# floor.net
KiCad netlist of a schematic drawn in EAGLE
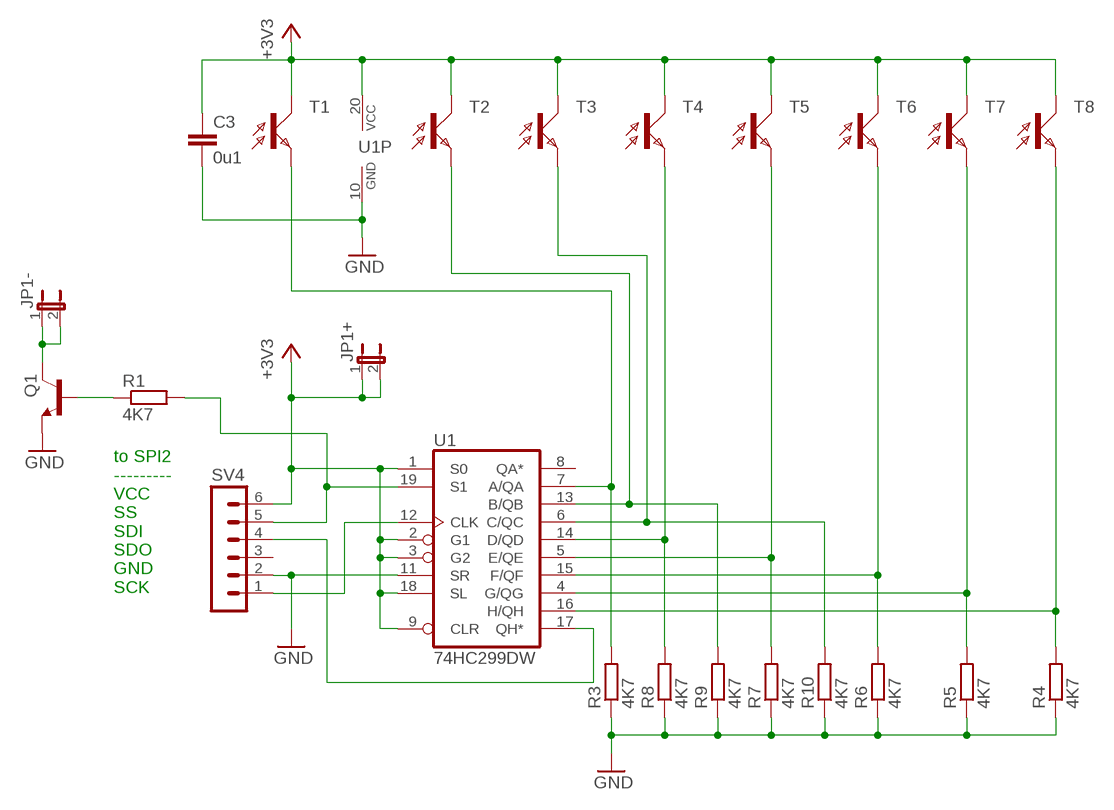
[diagram p0: schematic, sheet 1]

(export (version "E")
  (design (tool "Eeschema 10.0.6"))
  (components
    (comp (ref "C3")
      (value "0u1")
      (footprint "eagle-import:C0805")
      (libsource (lib "eagle-import") (part "C-EUC0805"))
    )
    (comp (ref "JP1+")
      (value "JP1E")
      (footprint "eagle-import:JP1")
      (libsource (lib "eagle-import") (part "JP1E"))
    )
    (comp (ref "JP1-")
      (value "JP1E")
      (footprint "eagle-import:JP1")
      (libsource (lib "eagle-import") (part "JP1E"))
    )
    (comp (ref "Q1")
      (value "BC817-25SMD")
      (footprint "eagle-import:SOT23-BEC")
      (libsource (lib "eagle-import") (part "BC817SMD-25"))
    )
    (comp (ref "R1")
      (value "4K7")
      (footprint "eagle-import:M0805")
      (libsource (lib "eagle-import") (part "R-EU_M0805"))
    )
    (comp (ref "R3")
      (value "4K7")
      (footprint "eagle-import:M0805")
      (libsource (lib "eagle-import") (part "R-EU_M0805"))
    )
    (comp (ref "R4")
      (value "4K7")
      (footprint "eagle-import:M0805")
      (libsource (lib "eagle-import") (part "R-EU_M0805"))
    )
    (comp (ref "R5")
      (value "4K7")
      (footprint "eagle-import:M0805")
      (libsource (lib "eagle-import") (part "R-EU_M0805"))
    )
    (comp (ref "R6")
      (value "4K7")
      (footprint "eagle-import:M0805")
      (libsource (lib "eagle-import") (part "R-EU_M0805"))
    )
    (comp (ref "R7")
      (value "4K7")
      (footprint "eagle-import:M0805")
      (libsource (lib "eagle-import") (part "R-EU_M0805"))
    )
    (comp (ref "R8")
      (value "4K7")
      (footprint "eagle-import:M0805")
      (libsource (lib "eagle-import") (part "R-EU_M0805"))
    )
    (comp (ref "R9")
      (value "4K7")
      (footprint "eagle-import:M0805")
      (libsource (lib "eagle-import") (part "R-EU_M0805"))
    )
    (comp (ref "R10")
      (value "4K7")
      (footprint "eagle-import:M0805")
      (libsource (lib "eagle-import") (part "R-EU_M0805"))
    )
    (comp (ref "SV4")
      (value "MA06-1")
      (footprint "eagle-import:MA06-1")
      (libsource (lib "eagle-import") (part "MA06-1"))
    )
    (comp (ref "T1")
      (value "PT17-21B")
      (footprint "eagle-import:CHIPLED_0805")
      (libsource (lib "eagle-import") (part "PHOTOTRANSISTOR"))
    )
    (comp (ref "T2")
      (value "PT17-21B")
      (footprint "eagle-import:CHIPLED_0805")
      (libsource (lib "eagle-import") (part "PHOTOTRANSISTOR"))
    )
    (comp (ref "T3")
      (value "PT17-21B")
      (footprint "eagle-import:CHIPLED_0805")
      (libsource (lib "eagle-import") (part "PHOTOTRANSISTOR"))
    )
    (comp (ref "T4")
      (value "PT17-21B")
      (footprint "eagle-import:CHIPLED_0805")
      (libsource (lib "eagle-import") (part "PHOTOTRANSISTOR"))
    )
    (comp (ref "T5")
      (value "PT17-21B")
      (footprint "eagle-import:CHIPLED_0805")
      (libsource (lib "eagle-import") (part "PHOTOTRANSISTOR"))
    )
    (comp (ref "T6")
      (value "PT17-21B")
      (footprint "eagle-import:CHIPLED_0805")
      (libsource (lib "eagle-import") (part "PHOTOTRANSISTOR"))
    )
    (comp (ref "T7")
      (value "PT17-21B")
      (footprint "eagle-import:CHIPLED_0805")
      (libsource (lib "eagle-import") (part "PHOTOTRANSISTOR"))
    )
    (comp (ref "T8")
      (value "PT17-21B")
      (footprint "eagle-import:CHIPLED_0805")
      (libsource (lib "eagle-import") (part "PHOTOTRANSISTOR"))
    )
    (comp (ref "U1")
      (value "74HC299DW")
      (footprint "eagle-import:SO20W")
      (libsource (lib "eagle-import") (part "74299DWHC"))
    )
  )
  (nets
    (net (code "1") (name "+3V3") (class "Default")
      (node (ref "C3") (pin "1") (pinfunction "1_1") (pintype "passive"))
      (node (ref "JP1+") (pin "1") (pinfunction "1_1") (pintype "passive"))
      (node (ref "JP1+") (pin "2") (pinfunction "2_2") (pintype "passive"))
      (node (ref "SV4") (pin "6") (pinfunction "6_6") (pintype "passive"))
      (node (ref "T1") (pin "C") (pinfunction "C_C") (pintype "passive"))
      (node (ref "T2") (pin "C") (pinfunction "C_C") (pintype "passive"))
      (node (ref "T3") (pin "C") (pinfunction "C_C") (pintype "passive"))
      (node (ref "T4") (pin "C") (pinfunction "C_C") (pintype "passive"))
      (node (ref "T5") (pin "C") (pinfunction "C_C") (pintype "passive"))
      (node (ref "T6") (pin "C") (pinfunction "C_C") (pintype "passive"))
      (node (ref "T7") (pin "C") (pinfunction "C_C") (pintype "passive"))
      (node (ref "T8") (pin "C") (pinfunction "C_C") (pintype "passive"))
      (node (ref "U1") (pin "1") (pinfunction "S0_1") (pintype "input"))
      (node (ref "U1") (pin "18") (pinfunction "SL_18") (pintype "input"))
      (node (ref "U1") (pin "2") (pinfunction "G1_2") (pintype "input"))
      (node (ref "U1") (pin "20") (pinfunction "VCC_20") (pintype "power_in"))
      (node (ref "U1") (pin "3") (pinfunction "G2_3") (pintype "input"))
      (node (ref "U1") (pin "9") (pinfunction "CLR_9") (pintype "input"))
    )
    (net (code "2") (name "GND") (class "Default")
      (node (ref "C3") (pin "2") (pinfunction "2_2") (pintype "passive"))
      (node (ref "Q1") (pin "E") (pinfunction "E_E") (pintype "passive"))
      (node (ref "R10") (pin "1") (pinfunction "1_1") (pintype "passive"))
      (node (ref "R3") (pin "1") (pinfunction "1_1") (pintype "passive"))
      (node (ref "R4") (pin "1") (pinfunction "1_1") (pintype "passive"))
      (node (ref "R5") (pin "1") (pinfunction "1_1") (pintype "passive"))
      (node (ref "R6") (pin "1") (pinfunction "1_1") (pintype "passive"))
      (node (ref "R7") (pin "1") (pinfunction "1_1") (pintype "passive"))
      (node (ref "R8") (pin "1") (pinfunction "1_1") (pintype "passive"))
      (node (ref "R9") (pin "1") (pinfunction "1_1") (pintype "passive"))
      (node (ref "SV4") (pin "2") (pinfunction "2_2") (pintype "passive"))
      (node (ref "U1") (pin "10") (pinfunction "GND_10") (pintype "power_in"))
      (node (ref "U1") (pin "11") (pinfunction "SR_11") (pintype "input"))
    )
    (net (code "3") (name "Net-(JP1--Pad1)") (class "Default")
      (node (ref "JP1-") (pin "1") (pinfunction "1_1") (pintype "passive"))
      (node (ref "JP1-") (pin "2") (pinfunction "2_2") (pintype "passive"))
      (node (ref "Q1") (pin "C") (pinfunction "C_C") (pintype "passive"))
    )
    (net (code "4") (name "Net-(Q1-PadB)") (class "Default")
      (node (ref "Q1") (pin "B") (pinfunction "B_B") (pintype "passive"))
      (node (ref "R1") (pin "1") (pinfunction "1_1") (pintype "passive"))
    )
    (net (code "5") (name "Net-(T1-E)") (class "Default")
      (node (ref "R3") (pin "2") (pinfunction "2_2") (pintype "passive"))
      (node (ref "T1") (pin "A") (pinfunction "E_A") (pintype "passive"))
      (node (ref "U1") (pin "7") (pinfunction "A/QA_7") (pintype "bidirectional"))
    )
    (net (code "6") (name "Net-(T2-E)") (class "Default")
      (node (ref "R9") (pin "2") (pinfunction "2_2") (pintype "passive"))
      (node (ref "T2") (pin "A") (pinfunction "E_A") (pintype "passive"))
      (node (ref "U1") (pin "13") (pinfunction "B/QB_13") (pintype "bidirectional"))
    )
    (net (code "7") (name "Net-(T3-E)") (class "Default")
      (node (ref "R10") (pin "2") (pinfunction "2_2") (pintype "passive"))
      (node (ref "T3") (pin "A") (pinfunction "E_A") (pintype "passive"))
      (node (ref "U1") (pin "6") (pinfunction "C/QC_6") (pintype "bidirectional"))
    )
    (net (code "8") (name "Net-(T4-E)") (class "Default")
      (node (ref "R8") (pin "2") (pinfunction "2_2") (pintype "passive"))
      (node (ref "T4") (pin "A") (pinfunction "E_A") (pintype "passive"))
      (node (ref "U1") (pin "14") (pinfunction "D/QD_14") (pintype "bidirectional"))
    )
    (net (code "9") (name "Net-(T5-E)") (class "Default")
      (node (ref "R7") (pin "2") (pinfunction "2_2") (pintype "passive"))
      (node (ref "T5") (pin "A") (pinfunction "E_A") (pintype "passive"))
      (node (ref "U1") (pin "5") (pinfunction "E/QE_5") (pintype "bidirectional"))
    )
    (net (code "10") (name "Net-(T6-E)") (class "Default")
      (node (ref "R6") (pin "2") (pinfunction "2_2") (pintype "passive"))
      (node (ref "T6") (pin "A") (pinfunction "E_A") (pintype "passive"))
      (node (ref "U1") (pin "15") (pinfunction "F/QF_15") (pintype "bidirectional"))
    )
    (net (code "11") (name "Net-(T7-E)") (class "Default")
      (node (ref "R5") (pin "2") (pinfunction "2_2") (pintype "passive"))
      (node (ref "T7") (pin "A") (pinfunction "E_A") (pintype "passive"))
      (node (ref "U1") (pin "4") (pinfunction "G/QG_4") (pintype "bidirectional"))
    )
    (net (code "12") (name "Net-(T8-E)") (class "Default")
      (node (ref "R4") (pin "2") (pinfunction "2_2") (pintype "passive"))
      (node (ref "T8") (pin "A") (pinfunction "E_A") (pintype "passive"))
      (node (ref "U1") (pin "16") (pinfunction "H/QH_16") (pintype "bidirectional"))
    )
    (net (code "13") (name "Net-(U1A-CLK)") (class "Default")
      (node (ref "SV4") (pin "1") (pinfunction "1_1") (pintype "passive"))
      (node (ref "U1") (pin "12") (pinfunction "CLK_12") (pintype "input"))
    )
    (net (code "14") (name "Net-(U1A-QH*)") (class "Default")
      (node (ref "SV4") (pin "4") (pinfunction "4_4") (pintype "passive"))
      (node (ref "U1") (pin "17") (pinfunction "QH*_17") (pintype "output"))
    )
    (net (code "15") (name "Net-(U1A-S1)") (class "Default")
      (node (ref "R1") (pin "2") (pinfunction "2_2") (pintype "passive"))
      (node (ref "SV4") (pin "5") (pinfunction "5_5") (pintype "passive"))
      (node (ref "U1") (pin "19") (pinfunction "S1_19") (pintype "input"))
    )
    (net (code "16") (name "unconnected-(SV4-Pad3)") (class "Default")
      (node (ref "SV4") (pin "3") (pinfunction "3_3") (pintype "passive"))
    )
    (net (code "17") (name "unconnected-(U1A-QA*-Pad8)") (class "Default")
      (node (ref "U1") (pin "8") (pinfunction "QA*_8") (pintype "output"))
    )
  )
)
